# led.net
KiCad netlist of a schematic drawn in EAGLE
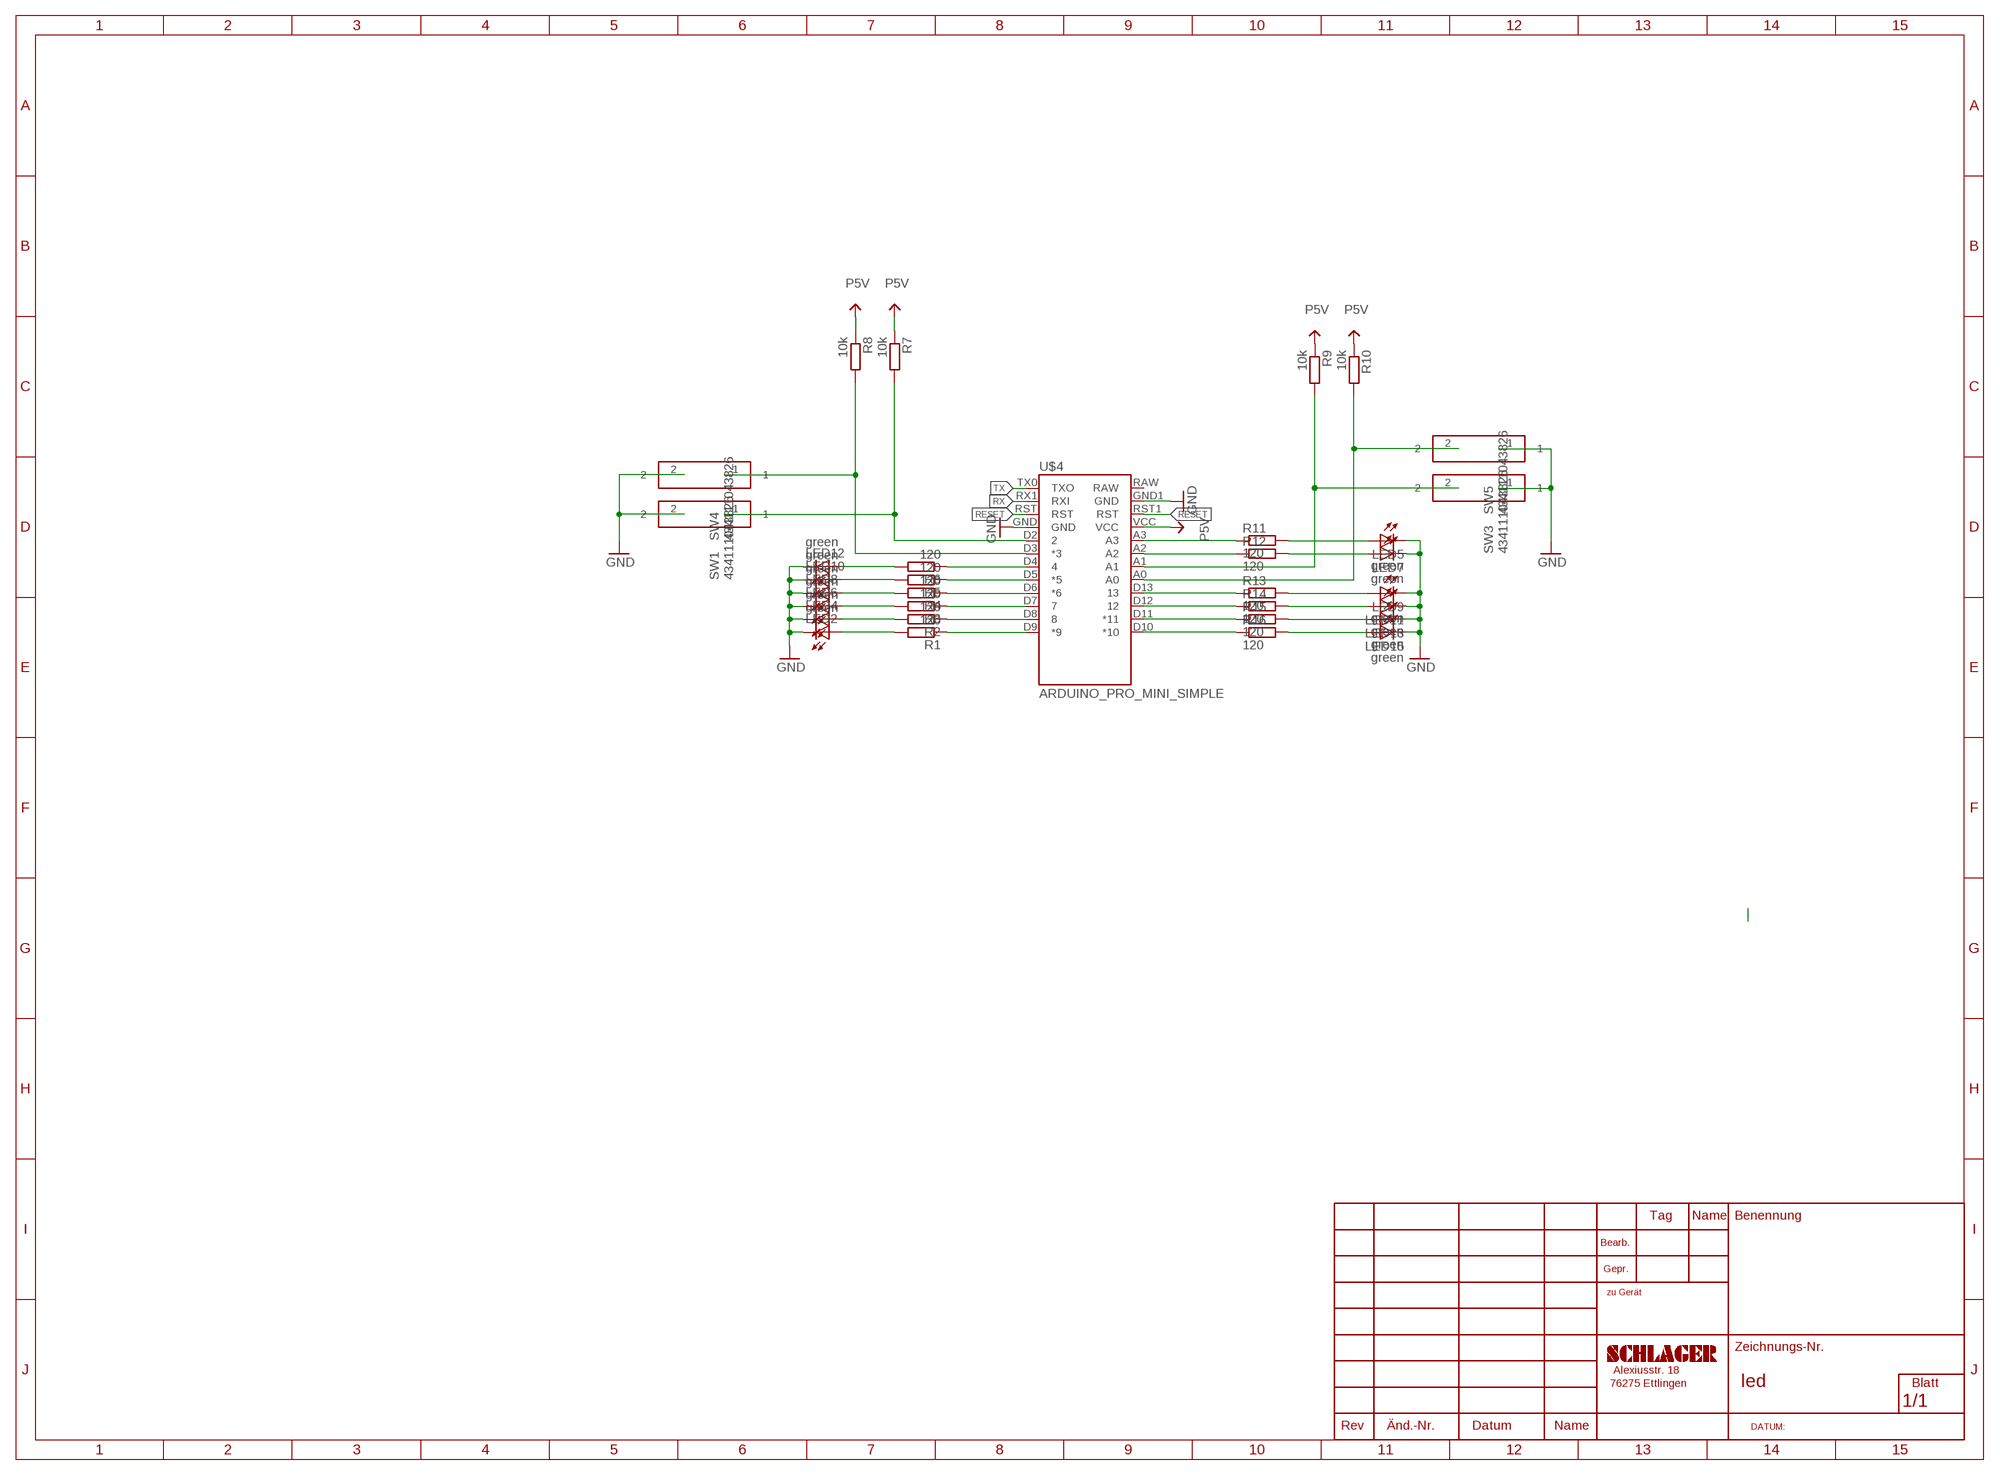
[diagram p0: schematic, sheet 1]

(export (version "E")
  (design (tool "Eeschema 10.0.6"))
  (components
    (comp (ref "LED2")
      (value "green")
      (footprint "eagle-import:CHIPLED_0805")
      (libsource (lib "eagle-import") (part "LEDCHIPLED_0805"))
    )
    (comp (ref "LED4")
      (value "green")
      (footprint "eagle-import:CHIPLED_0805")
      (libsource (lib "eagle-import") (part "LEDCHIPLED_0805"))
    )
    (comp (ref "LED5")
      (value "green")
      (footprint "eagle-import:CHIPLED_0805")
      (libsource (lib "eagle-import") (part "LEDCHIPLED_0805"))
    )
    (comp (ref "LED6")
      (value "green")
      (footprint "eagle-import:CHIPLED_0805")
      (libsource (lib "eagle-import") (part "LEDCHIPLED_0805"))
    )
    (comp (ref "LED7")
      (value "green")
      (footprint "eagle-import:CHIPLED_0805")
      (libsource (lib "eagle-import") (part "LEDCHIPLED_0805"))
    )
    (comp (ref "LED8")
      (value "green")
      (footprint "eagle-import:CHIPLED_0805")
      (libsource (lib "eagle-import") (part "LEDCHIPLED_0805"))
    )
    (comp (ref "LED9")
      (value "green")
      (footprint "eagle-import:CHIPLED_0805")
      (libsource (lib "eagle-import") (part "LEDCHIPLED_0805"))
    )
    (comp (ref "LED10")
      (value "green")
      (footprint "eagle-import:CHIPLED_0805")
      (libsource (lib "eagle-import") (part "LEDCHIPLED_0805"))
    )
    (comp (ref "LED11")
      (value "green")
      (footprint "eagle-import:CHIPLED_0805")
      (libsource (lib "eagle-import") (part "LEDCHIPLED_0805"))
    )
    (comp (ref "LED12")
      (value "green")
      (footprint "eagle-import:CHIPLED_0805")
      (libsource (lib "eagle-import") (part "LEDCHIPLED_0805"))
    )
    (comp (ref "LED13")
      (value "green")
      (footprint "eagle-import:CHIPLED_0805")
      (libsource (lib "eagle-import") (part "LEDCHIPLED_0805"))
    )
    (comp (ref "LED15")
      (value "green")
      (footprint "eagle-import:CHIPLED_0805")
      (libsource (lib "eagle-import") (part "LEDCHIPLED_0805"))
    )
    (comp (ref "R1")
      (value "120")
      (footprint "eagle-import:R0805")
      (libsource (lib "eagle-import") (part "R-EU_R0805"))
    )
    (comp (ref "R2")
      (value "120")
      (footprint "eagle-import:R0805")
      (libsource (lib "eagle-import") (part "R-EU_R0805"))
    )
    (comp (ref "R3")
      (value "120")
      (footprint "eagle-import:R0805")
      (libsource (lib "eagle-import") (part "R-EU_R0805"))
    )
    (comp (ref "R4")
      (value "120")
      (footprint "eagle-import:R0805")
      (libsource (lib "eagle-import") (part "R-EU_R0805"))
    )
    (comp (ref "R5")
      (value "120")
      (footprint "eagle-import:R0805")
      (libsource (lib "eagle-import") (part "R-EU_R0805"))
    )
    (comp (ref "R6")
      (value "120")
      (footprint "eagle-import:R0805")
      (libsource (lib "eagle-import") (part "R-EU_R0805"))
    )
    (comp (ref "R7")
      (value "10k")
      (footprint "eagle-import:R0805")
      (libsource (lib "eagle-import") (part "R-EU_R0805"))
    )
    (comp (ref "R8")
      (value "10k")
      (footprint "eagle-import:R0805")
      (libsource (lib "eagle-import") (part "R-EU_R0805"))
    )
    (comp (ref "R9")
      (value "10k")
      (footprint "eagle-import:R0805")
      (libsource (lib "eagle-import") (part "R-EU_R0805"))
    )
    (comp (ref "R10")
      (value "10k")
      (footprint "eagle-import:R0805")
      (libsource (lib "eagle-import") (part "R-EU_R0805"))
    )
    (comp (ref "R11")
      (value "120")
      (footprint "eagle-import:R0805")
      (libsource (lib "eagle-import") (part "R-EU_R0805"))
    )
    (comp (ref "R12")
      (value "120")
      (footprint "eagle-import:R0805")
      (libsource (lib "eagle-import") (part "R-EU_R0805"))
    )
    (comp (ref "R13")
      (value "120")
      (footprint "eagle-import:R0805")
      (libsource (lib "eagle-import") (part "R-EU_R0805"))
    )
    (comp (ref "R14")
      (value "120")
      (footprint "eagle-import:R0805")
      (libsource (lib "eagle-import") (part "R-EU_R0805"))
    )
    (comp (ref "R15")
      (value "120")
      (footprint "eagle-import:R0805")
      (libsource (lib "eagle-import") (part "R-EU_R0805"))
    )
    (comp (ref "R16")
      (value "120")
      (footprint "eagle-import:R0805")
      (libsource (lib "eagle-import") (part "R-EU_R0805"))
    )
    (comp (ref "SW1")
      (value "434111043826")
      (footprint "eagle-import:434111043826")
      (libsource (lib "eagle-import") (part "434111043826"))
    )
    (comp (ref "SW3")
      (value "434111043826")
      (footprint "eagle-import:434111043826")
      (libsource (lib "eagle-import") (part "434111043826"))
    )
    (comp (ref "SW4")
      (value "434111043826")
      (footprint "eagle-import:434111043826")
      (libsource (lib "eagle-import") (part "434111043826"))
    )
    (comp (ref "SW5")
      (value "434111043826")
      (footprint "eagle-import:434111043826")
      (libsource (lib "eagle-import") (part "434111043826"))
    )
    (comp (ref "U$4")
      (value "ARDUINO_PRO_MINI_SIMPLE")
      (footprint "eagle-import:PRO_MINI_SIMPLE")
      (libsource (lib "eagle-import") (part "ARDUINO_PRO_MINI_SIMPLE"))
    )
  )
  (nets
    (net (code "1") (name "GND") (class "Default")
      (node (ref "LED10") (pin "C") (pinfunction "C_C") (pintype "passive"))
      (node (ref "LED11") (pin "C") (pinfunction "C_C") (pintype "passive"))
      (node (ref "LED12") (pin "C") (pinfunction "C_C") (pintype "passive"))
      (node (ref "LED13") (pin "C") (pinfunction "C_C") (pintype "passive"))
      (node (ref "LED15") (pin "C") (pinfunction "C_C") (pintype "passive"))
      (node (ref "LED2") (pin "C") (pinfunction "C_C") (pintype "passive"))
      (node (ref "LED4") (pin "C") (pinfunction "C_C") (pintype "passive"))
      (node (ref "LED5") (pin "C") (pinfunction "C_C") (pintype "passive"))
      (node (ref "LED6") (pin "C") (pinfunction "C_C") (pintype "passive"))
      (node (ref "LED7") (pin "C") (pinfunction "C_C") (pintype "passive"))
      (node (ref "LED8") (pin "C") (pinfunction "C_C") (pintype "passive"))
      (node (ref "LED9") (pin "C") (pinfunction "C_C") (pintype "passive"))
      (node (ref "SW1") (pin "2") (pinfunction "2_2") (pintype "bidirectional"))
      (node (ref "SW3") (pin "1") (pinfunction "1_1") (pintype "bidirectional"))
      (node (ref "SW4") (pin "2") (pinfunction "2_2") (pintype "bidirectional"))
      (node (ref "SW5") (pin "1") (pinfunction "1_1") (pintype "bidirectional"))
      (node (ref "U$4") (pin "GND") (pinfunction "GND_GND") (pintype "bidirectional"))
      (node (ref "U$4") (pin "GND1") (pinfunction "GND_GND1") (pintype "bidirectional"))
    )
    (net (code "2") (name "Net-(LED2-PadA)") (class "Default")
      (node (ref "LED2") (pin "A") (pinfunction "A_A") (pintype "passive"))
      (node (ref "R1") (pin "2") (pinfunction "2_2") (pintype "passive"))
    )
    (net (code "3") (name "Net-(LED4-PadA)") (class "Default")
      (node (ref "LED4") (pin "A") (pinfunction "A_A") (pintype "passive"))
      (node (ref "R2") (pin "2") (pinfunction "2_2") (pintype "passive"))
    )
    (net (code "4") (name "Net-(LED5-PadA)") (class "Default")
      (node (ref "LED5") (pin "A") (pinfunction "A_A") (pintype "passive"))
      (node (ref "R11") (pin "2") (pinfunction "2_2") (pintype "passive"))
    )
    (net (code "5") (name "Net-(LED6-PadA)") (class "Default")
      (node (ref "LED6") (pin "A") (pinfunction "A_A") (pintype "passive"))
      (node (ref "R3") (pin "2") (pinfunction "2_2") (pintype "passive"))
    )
    (net (code "6") (name "Net-(LED7-PadA)") (class "Default")
      (node (ref "LED7") (pin "A") (pinfunction "A_A") (pintype "passive"))
      (node (ref "R12") (pin "2") (pinfunction "2_2") (pintype "passive"))
    )
    (net (code "7") (name "Net-(LED8-PadA)") (class "Default")
      (node (ref "LED8") (pin "A") (pinfunction "A_A") (pintype "passive"))
      (node (ref "R4") (pin "2") (pinfunction "2_2") (pintype "passive"))
    )
    (net (code "8") (name "Net-(LED9-PadA)") (class "Default")
      (node (ref "LED9") (pin "A") (pinfunction "A_A") (pintype "passive"))
      (node (ref "R13") (pin "2") (pinfunction "2_2") (pintype "passive"))
    )
    (net (code "9") (name "Net-(LED10-PadA)") (class "Default")
      (node (ref "LED10") (pin "A") (pinfunction "A_A") (pintype "passive"))
      (node (ref "R5") (pin "2") (pinfunction "2_2") (pintype "passive"))
    )
    (net (code "10") (name "Net-(LED11-PadA)") (class "Default")
      (node (ref "LED11") (pin "A") (pinfunction "A_A") (pintype "passive"))
      (node (ref "R14") (pin "2") (pinfunction "2_2") (pintype "passive"))
    )
    (net (code "11") (name "Net-(LED12-PadA)") (class "Default")
      (node (ref "LED12") (pin "A") (pinfunction "A_A") (pintype "passive"))
      (node (ref "R6") (pin "2") (pinfunction "2_2") (pintype "passive"))
    )
    (net (code "12") (name "Net-(LED13-PadA)") (class "Default")
      (node (ref "LED13") (pin "A") (pinfunction "A_A") (pintype "passive"))
      (node (ref "R15") (pin "2") (pinfunction "2_2") (pintype "passive"))
    )
    (net (code "13") (name "Net-(LED15-PadA)") (class "Default")
      (node (ref "LED15") (pin "A") (pinfunction "A_A") (pintype "passive"))
      (node (ref "R16") (pin "2") (pinfunction "2_2") (pintype "passive"))
    )
    (net (code "14") (name "Net-(R9-Pad2)") (class "Default")
      (node (ref "R9") (pin "2") (pinfunction "2_2") (pintype "passive"))
      (node (ref "SW3") (pin "2") (pinfunction "2_2") (pintype "bidirectional"))
      (node (ref "U$4") (pin "A1") (pinfunction "A1_A1") (pintype "bidirectional"))
    )
    (net (code "15") (name "Net-(R10-Pad2)") (class "Default")
      (node (ref "R10") (pin "2") (pinfunction "2_2") (pintype "passive"))
      (node (ref "SW5") (pin "2") (pinfunction "2_2") (pintype "bidirectional"))
      (node (ref "U$4") (pin "A0") (pinfunction "A0_A0") (pintype "bidirectional"))
    )
    (net (code "16") (name "Net-(R11-Pad1)") (class "Default")
      (node (ref "R11") (pin "1") (pinfunction "1_1") (pintype "passive"))
      (node (ref "U$4") (pin "A3") (pinfunction "A3_A3") (pintype "bidirectional"))
    )
    (net (code "17") (name "Net-(R12-Pad1)") (class "Default")
      (node (ref "R12") (pin "1") (pinfunction "1_1") (pintype "passive"))
      (node (ref "U$4") (pin "A2") (pinfunction "A2_A2") (pintype "bidirectional"))
    )
    (net (code "18") (name "Net-(U$4-*3)") (class "Default")
      (node (ref "R8") (pin "2") (pinfunction "2_2") (pintype "passive"))
      (node (ref "SW4") (pin "1") (pinfunction "1_1") (pintype "bidirectional"))
      (node (ref "U$4") (pin "D3") (pinfunction "*3_D3") (pintype "bidirectional"))
    )
    (net (code "19") (name "Net-(U$4-*5)") (class "Default")
      (node (ref "R5") (pin "1") (pinfunction "1_1") (pintype "passive"))
      (node (ref "U$4") (pin "D5") (pinfunction "*5_D5") (pintype "bidirectional"))
    )
    (net (code "20") (name "Net-(U$4-*6)") (class "Default")
      (node (ref "R4") (pin "1") (pinfunction "1_1") (pintype "passive"))
      (node (ref "U$4") (pin "D6") (pinfunction "*6_D6") (pintype "bidirectional"))
    )
    (net (code "21") (name "Net-(U$4-*9)") (class "Default")
      (node (ref "R1") (pin "1") (pinfunction "1_1") (pintype "passive"))
      (node (ref "U$4") (pin "D9") (pinfunction "*9_D9") (pintype "bidirectional"))
    )
    (net (code "22") (name "Net-(U$4-*10)") (class "Default")
      (node (ref "R16") (pin "1") (pinfunction "1_1") (pintype "passive"))
      (node (ref "U$4") (pin "D10") (pinfunction "*10_D10") (pintype "bidirectional"))
    )
    (net (code "23") (name "Net-(U$4-*11)") (class "Default")
      (node (ref "R15") (pin "1") (pinfunction "1_1") (pintype "passive"))
      (node (ref "U$4") (pin "D11") (pinfunction "*11_D11") (pintype "bidirectional"))
    )
    (net (code "24") (name "Net-(U$4-2)") (class "Default")
      (node (ref "R7") (pin "2") (pinfunction "2_2") (pintype "passive"))
      (node (ref "SW1") (pin "1") (pinfunction "1_1") (pintype "bidirectional"))
      (node (ref "U$4") (pin "D2") (pinfunction "2_D2") (pintype "bidirectional"))
    )
    (net (code "25") (name "Net-(U$4-4)") (class "Default")
      (node (ref "R6") (pin "1") (pinfunction "1_1") (pintype "passive"))
      (node (ref "U$4") (pin "D4") (pinfunction "4_D4") (pintype "bidirectional"))
    )
    (net (code "26") (name "Net-(U$4-7)") (class "Default")
      (node (ref "R3") (pin "1") (pinfunction "1_1") (pintype "passive"))
      (node (ref "U$4") (pin "D7") (pinfunction "7_D7") (pintype "bidirectional"))
    )
    (net (code "27") (name "Net-(U$4-8)") (class "Default")
      (node (ref "R2") (pin "1") (pinfunction "1_1") (pintype "passive"))
      (node (ref "U$4") (pin "D8") (pinfunction "8_D8") (pintype "bidirectional"))
    )
    (net (code "28") (name "Net-(U$4-12)") (class "Default")
      (node (ref "R14") (pin "1") (pinfunction "1_1") (pintype "passive"))
      (node (ref "U$4") (pin "D12") (pinfunction "12_D12") (pintype "bidirectional"))
    )
    (net (code "29") (name "Net-(U$4-13)") (class "Default")
      (node (ref "R13") (pin "1") (pinfunction "1_1") (pintype "passive"))
      (node (ref "U$4") (pin "D13") (pinfunction "13_D13") (pintype "bidirectional"))
    )
    (net (code "30") (name "P5V") (class "Default")
      (node (ref "R10") (pin "1") (pinfunction "1_1") (pintype "passive"))
      (node (ref "R7") (pin "1") (pinfunction "1_1") (pintype "passive"))
      (node (ref "R8") (pin "1") (pinfunction "1_1") (pintype "passive"))
      (node (ref "R9") (pin "1") (pinfunction "1_1") (pintype "passive"))
      (node (ref "U$4") (pin "VCC") (pinfunction "VCC_VCC") (pintype "bidirectional"))
    )
    (net (code "31") (name "RESET") (class "Default")
      (node (ref "U$4") (pin "RST") (pinfunction "RST_RST") (pintype "bidirectional"))
      (node (ref "U$4") (pin "RST1") (pinfunction "RST_RST1") (pintype "bidirectional"))
    )
    (net (code "32") (name "RX") (class "Default")
      (node (ref "U$4") (pin "RX1") (pinfunction "RXI_RX1") (pintype "bidirectional"))
    )
    (net (code "33") (name "TX") (class "Default")
      (node (ref "U$4") (pin "TX0") (pinfunction "TXO_TX0") (pintype "bidirectional"))
    )
    (net (code "34") (name "unconnected-(U$4-PadRAW)") (class "Default")
      (node (ref "U$4") (pin "RAW") (pinfunction "RAW_RAW") (pintype "bidirectional"))
    )
  )
)
